# simple-loop-screws.net
KiCad netlist of a schematic drawn in EAGLE
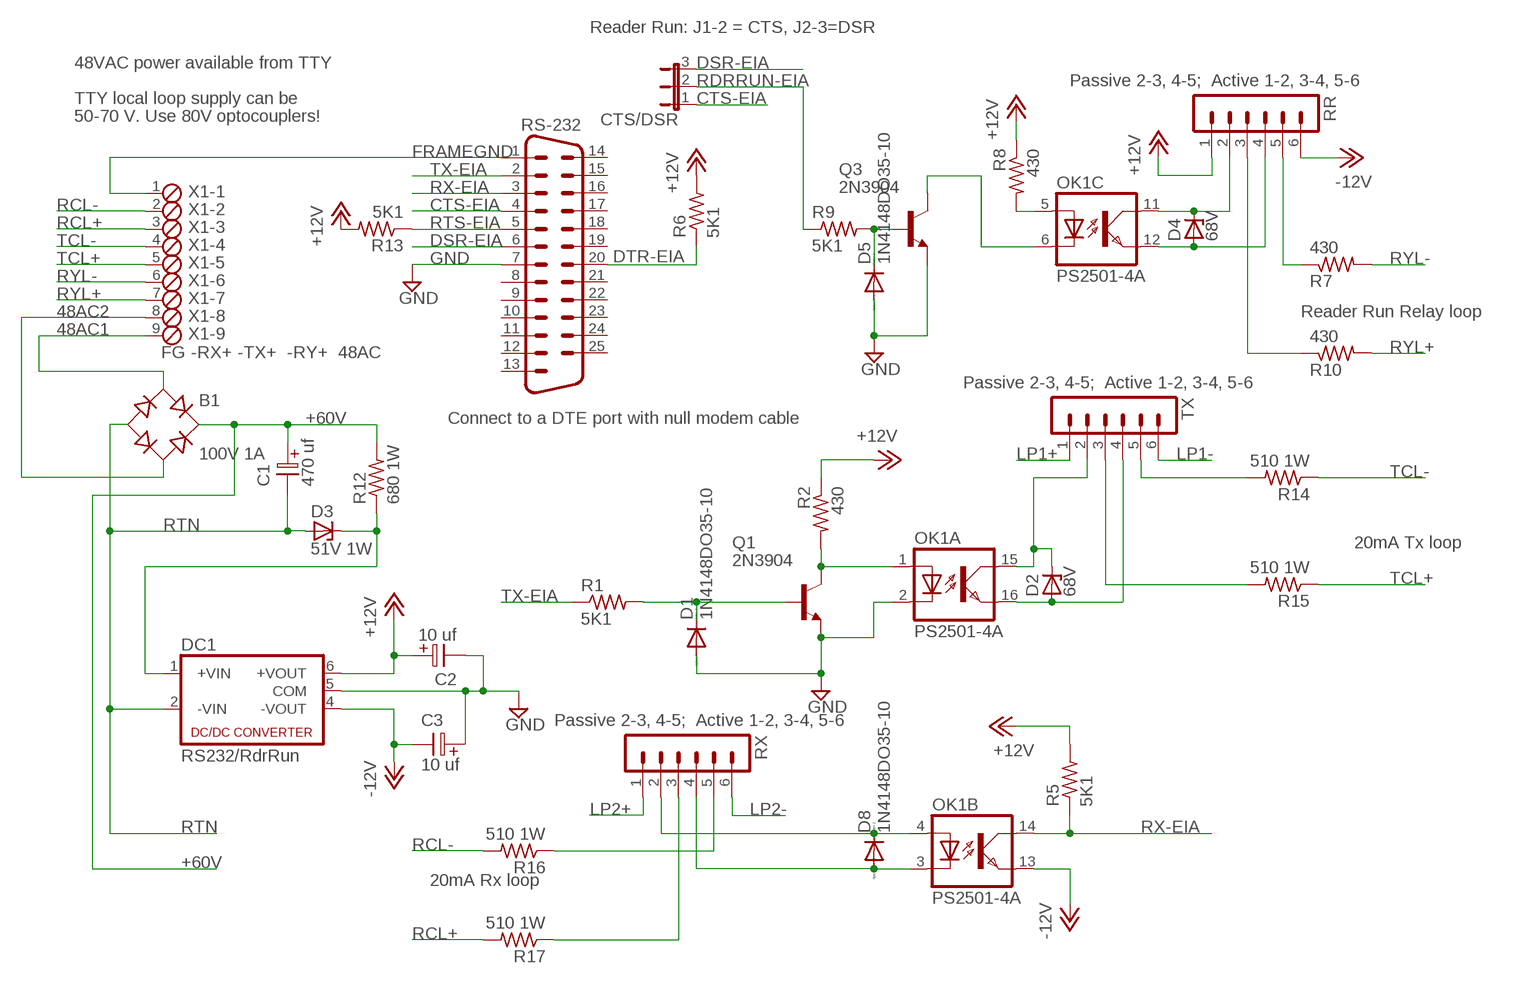
[diagram p0: schematic, sheet 1]
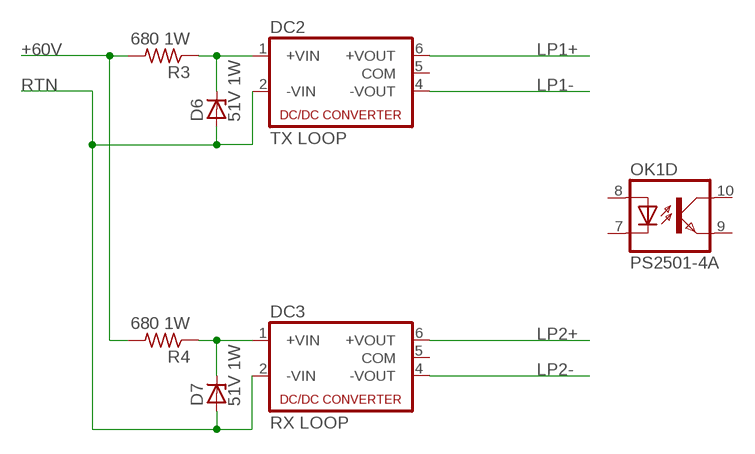
[diagram p1: schematic, sheet 2]

(export (version "E")
  (design (tool "Eeschema 10.0.6"))
  (components
    (comp (ref "D6")
      (value "51V 1W")
      (footprint "eagle-import:DO41Z10")
      (libsource (lib "eagle-import") (part "ZENER-DIODEDO41Z10"))
    )
    (comp (ref "D7")
      (value "51V 1W")
      (footprint "eagle-import:DO41Z10")
      (libsource (lib "eagle-import") (part "ZENER-DIODEDO41Z10"))
    )
    (comp (ref "DC2")
      (value "TX LOOP")
      (footprint "eagle-import:NMA")
      (fields (field (name "MF") "C & D TECHNOLOGIES, INC") (field (name "MPN") "NMA0515SC"))
      (libsource (lib "eagle-import") (part "NMA"))
    )
    (comp (ref "DC3")
      (value "RX LOOP")
      (footprint "eagle-import:NMA")
      (fields (field (name "MF") "C & D TECHNOLOGIES, INC") (field (name "MPN") "NMA0515SC"))
      (libsource (lib "eagle-import") (part "NMA"))
    )
    (comp (ref "OK1")
      (value "PS2501-4A")
      (footprint "eagle-import:DIL16")
      (fields (field (name "MF") "VISHAY/TELEFUNKEN") (field (name "MPN") "ILQ1"))
      (libsource (lib "eagle-import") (part "ILQ1"))
    )
    (comp (ref "R3")
      (value "680 1W")
      (footprint "eagle-import:P0817V")
      (libsource (lib "eagle-import") (part "R-US_0817/7V"))
    )
    (comp (ref "R4")
      (value "680 1W")
      (footprint "eagle-import:P0817V")
      (libsource (lib "eagle-import") (part "R-US_0817/7V"))
    )
    (comp (ref "B1")
      (value "100V 1A")
      (footprint "eagle-import:RB1A")
      (libsource (lib "eagle-import") (part "RB1A"))
    )
    (comp (ref "C1")
      (value "470 uf")
      (footprint "eagle-import:ES-7,5")
      (libsource (lib "eagle-import") (part "ELC-7,5"))
    )
    (comp (ref "C2")
      (value "10 uf")
      (footprint "eagle-import:ES-2,5")
      (libsource (lib "eagle-import") (part "ELC-2,5"))
    )
    (comp (ref "C3")
      (value "10 uf")
      (footprint "eagle-import:ES-2,5")
      (libsource (lib "eagle-import") (part "ELC-2,5"))
    )
    (comp (ref "CTS/DSR")
      (value "JP2E")
      (footprint "eagle-import:JP2")
      (libsource (lib "eagle-import") (part "JP2E"))
    )
    (comp (ref "D1")
      (value "1N4148DO35-10")
      (footprint "eagle-import:DO35-10")
      (libsource (lib "eagle-import") (part "1N4148DO35-10"))
    )
    (comp (ref "D2")
      (value "68V")
      (footprint "eagle-import:DO41Z10")
      (libsource (lib "eagle-import") (part "ZENER-DIODEDO41Z10"))
    )
    (comp (ref "D3")
      (value "51V 1W")
      (footprint "eagle-import:DO41Z10")
      (libsource (lib "eagle-import") (part "ZENER-DIODEDO41Z10"))
    )
    (comp (ref "D4")
      (value "68V")
      (footprint "eagle-import:DO41Z10")
      (libsource (lib "eagle-import") (part "ZENER-DIODEDO41Z10"))
    )
    (comp (ref "D5")
      (value "1N4148DO35-10")
      (footprint "eagle-import:DO35-10")
      (libsource (lib "eagle-import") (part "1N4148DO35-10"))
    )
    (comp (ref "D8")
      (value "1N4148DO35-10")
      (footprint "eagle-import:DO35-10")
      (libsource (lib "eagle-import") (part "1N4148DO35-10"))
    )
    (comp (ref "DC1")
      (value "RS232/RdrRun")
      (footprint "eagle-import:NMA")
      (fields (field (name "MF") "C & D TECHNOLOGIES, INC") (field (name "MPN") "NMA0515SC"))
      (libsource (lib "eagle-import") (part "NMA"))
    )
    (comp (ref "Q1")
      (value "2N3904")
      (footprint "eagle-import:TO92")
      (libsource (lib "eagle-import") (part "2N3904"))
    )
    (comp (ref "Q3")
      (value "2N3904")
      (footprint "eagle-import:TO92")
      (libsource (lib "eagle-import") (part "2N3904"))
    )
    (comp (ref "R1")
      (value "5K1")
      (footprint "eagle-import:0207_10")
      (libsource (lib "eagle-import") (part "R-US_0207/10"))
    )
    (comp (ref "R2")
      (value "430")
      (footprint "eagle-import:0207_10")
      (libsource (lib "eagle-import") (part "R-US_0207/10"))
    )
    (comp (ref "R5")
      (value "5K1")
      (footprint "eagle-import:0207_10")
      (libsource (lib "eagle-import") (part "R-US_0207/10"))
    )
    (comp (ref "R6")
      (value "5K1")
      (footprint "eagle-import:0207_10")
      (libsource (lib "eagle-import") (part "R-US_0207/10"))
    )
    (comp (ref "R7")
      (value "430")
      (footprint "eagle-import:0207_10")
      (libsource (lib "eagle-import") (part "R-US_0207/10"))
    )
    (comp (ref "R8")
      (value "430")
      (footprint "eagle-import:0207_10")
      (libsource (lib "eagle-import") (part "R-US_0207/10"))
    )
    (comp (ref "R9")
      (value "5K1")
      (footprint "eagle-import:0207_10")
      (libsource (lib "eagle-import") (part "R-US_0207/10"))
    )
    (comp (ref "R10")
      (value "430")
      (footprint "eagle-import:0207_10")
      (libsource (lib "eagle-import") (part "R-US_0207/10"))
    )
    (comp (ref "R12")
      (value "680 1W")
      (footprint "eagle-import:P0817V")
      (libsource (lib "eagle-import") (part "R-US_0817/7V"))
    )
    (comp (ref "R13")
      (value "5K1")
      (footprint "eagle-import:0207_10")
      (libsource (lib "eagle-import") (part "R-US_0207/10"))
    )
    (comp (ref "R14")
      (value "510 1W")
      (footprint "eagle-import:P0817V")
      (libsource (lib "eagle-import") (part "R-US_0817/7V"))
    )
    (comp (ref "R15")
      (value "510 1W")
      (footprint "eagle-import:P0817V")
      (libsource (lib "eagle-import") (part "R-US_0817/7V"))
    )
    (comp (ref "R16")
      (value "510 1W")
      (footprint "eagle-import:P0817V")
      (libsource (lib "eagle-import") (part "R-US_0817/7V"))
    )
    (comp (ref "R17")
      (value "510 1W")
      (footprint "eagle-import:P0817V")
      (libsource (lib "eagle-import") (part "R-US_0817/7V"))
    )
    (comp (ref "RR")
      (value "MA06-1")
      (footprint "eagle-import:MA06-1")
      (libsource (lib "eagle-import") (part "MA06-1"))
    )
    (comp (ref "RS-232")
      (value "M25H")
      (footprint "eagle-import:M25H")
      (libsource (lib "eagle-import") (part "M25H"))
    )
    (comp (ref "RX")
      (value "MA06-1")
      (footprint "eagle-import:MA06-1")
      (libsource (lib "eagle-import") (part "MA06-1"))
    )
    (comp (ref "TX")
      (value "MA06-1")
      (footprint "eagle-import:MA06-1")
      (libsource (lib "eagle-import") (part "MA06-1"))
    )
    (comp (ref "X1")
      (value "FG -RX+ -TX+ -RY+ 48AC")
      (footprint "eagle-import:9POL254")
      (libsource (lib "eagle-import") (part "MPT9"))
    )
  )
  (nets
    (net (code "1") (name "+12V") (class "Default")
      (node (ref "C2") (pin "1") (pinfunction "1_1") (pintype "passive"))
      (node (ref "DC1") (pin "6") (pinfunction "+VOUT_6") (pintype "passive"))
      (node (ref "R13") (pin "2") (pinfunction "2_2") (pintype "passive"))
      (node (ref "R2") (pin "1") (pinfunction "1_1") (pintype "passive"))
      (node (ref "R5") (pin "2") (pinfunction "2_2") (pintype "passive"))
      (node (ref "R6") (pin "2") (pinfunction "2_2") (pintype "passive"))
      (node (ref "R8") (pin "1") (pinfunction "1_1") (pintype "passive"))
      (node (ref "RR") (pin "1") (pinfunction "1_1") (pintype "passive"))
    )
    (net (code "2") (name "+60V") (class "Default")
      (node (ref "B1") (pin "+") (pinfunction "+_+") (pintype "passive"))
      (node (ref "C1") (pin "1") (pinfunction "1_1") (pintype "passive"))
      (node (ref "R12") (pin "2") (pinfunction "2_2") (pintype "passive"))
      (node (ref "R3") (pin "2") (pinfunction "2_2") (pintype "passive"))
      (node (ref "R4") (pin "2") (pinfunction "2_2") (pintype "passive"))
    )
    (net (code "3") (name "-12V") (class "Default")
      (node (ref "C3") (pin "2") (pinfunction "2_2") (pintype "passive"))
      (node (ref "DC1") (pin "4") (pinfunction "-VOUT_4") (pintype "passive"))
      (node (ref "OK1") (pin "13") (pinfunction "EMIT_13") (pintype "passive"))
      (node (ref "RR") (pin "6") (pinfunction "6_6") (pintype "passive"))
    )
    (net (code "4") (name "48AC1") (class "Default")
      (node (ref "B1") (pin "AC1") (pinfunction "AC1_AC1") (pintype "passive"))
      (node (ref "X1") (pin "9") (pinfunction "1_9") (pintype "passive"))
    )
    (net (code "5") (name "48AC2") (class "Default")
      (node (ref "B1") (pin "AC2") (pinfunction "AC2_AC2") (pintype "passive"))
      (node (ref "X1") (pin "8") (pinfunction "1_8") (pintype "passive"))
    )
    (net (code "6") (name "CTS-EIA") (class "Default")
      (node (ref "CTS/DSR") (pin "1") (pinfunction "1_1") (pintype "passive"))
      (node (ref "RS-232") (pin "4") (pinfunction "4_4") (pintype "passive"))
    )
    (net (code "7") (name "DSR-EIA") (class "Default")
      (node (ref "CTS/DSR") (pin "3") (pinfunction "3_3") (pintype "passive"))
      (node (ref "RS-232") (pin "6") (pinfunction "6_6") (pintype "passive"))
    )
    (net (code "8") (name "DTR-EIA") (class "Default")
      (node (ref "R6") (pin "1") (pinfunction "1_1") (pintype "passive"))
      (node (ref "RS-232") (pin "20") (pinfunction "20_20") (pintype "passive"))
    )
    (net (code "9") (name "FRAMEGND") (class "Default")
      (node (ref "RS-232") (pin "1") (pinfunction "1_1") (pintype "passive"))
      (node (ref "X1") (pin "1") (pinfunction "1_1") (pintype "passive"))
    )
    (net (code "10") (name "GND") (class "Default")
      (node (ref "C2") (pin "2") (pinfunction "2_2") (pintype "passive"))
      (node (ref "C3") (pin "1") (pinfunction "1_1") (pintype "passive"))
      (node (ref "D1") (pin "A") (pinfunction "A_A") (pintype "passive"))
      (node (ref "D5") (pin "A") (pinfunction "A_A") (pintype "passive"))
      (node (ref "DC1") (pin "5") (pinfunction "COM_5") (pintype "passive"))
      (node (ref "OK1") (pin "2") (pinfunction "C_2") (pintype "passive"))
      (node (ref "Q1") (pin "3") (pinfunction "E_3") (pintype "passive"))
      (node (ref "Q3") (pin "3") (pinfunction "E_3") (pintype "passive"))
      (node (ref "RS-232") (pin "7") (pinfunction "7_7") (pintype "passive"))
    )
    (net (code "11") (name "LP1+") (class "Default")
      (node (ref "DC2") (pin "6") (pinfunction "+VOUT_6") (pintype "passive"))
      (node (ref "TX") (pin "1") (pinfunction "1_1") (pintype "passive"))
    )
    (net (code "12") (name "LP1-") (class "Default")
      (node (ref "DC2") (pin "4") (pinfunction "-VOUT_4") (pintype "passive"))
      (node (ref "TX") (pin "6") (pinfunction "6_6") (pintype "passive"))
    )
    (net (code "13") (name "LP2+") (class "Default")
      (node (ref "DC3") (pin "6") (pinfunction "+VOUT_6") (pintype "passive"))
      (node (ref "RX") (pin "1") (pinfunction "1_1") (pintype "passive"))
    )
    (net (code "14") (name "LP2-") (class "Default")
      (node (ref "DC3") (pin "4") (pinfunction "-VOUT_4") (pintype "passive"))
      (node (ref "RX") (pin "6") (pinfunction "6_6") (pintype "passive"))
    )
    (net (code "15") (name "Net-(DC1-+VIN)") (class "Default")
      (node (ref "D3") (pin "C") (pinfunction "C_C") (pintype "passive"))
      (node (ref "DC1") (pin "1") (pinfunction "+VIN_1") (pintype "passive"))
      (node (ref "R12") (pin "1") (pinfunction "1_1") (pintype "passive"))
    )
    (net (code "16") (name "Net-(DC2-+VIN)") (class "Default")
      (node (ref "D6") (pin "C") (pinfunction "C_C") (pintype "passive"))
      (node (ref "DC2") (pin "1") (pinfunction "+VIN_1") (pintype "passive"))
      (node (ref "R3") (pin "1") (pinfunction "1_1") (pintype "passive"))
    )
    (net (code "17") (name "Net-(DC3-+VIN)") (class "Default")
      (node (ref "D7") (pin "C") (pinfunction "C_C") (pintype "passive"))
      (node (ref "DC3") (pin "1") (pinfunction "+VIN_1") (pintype "passive"))
      (node (ref "R4") (pin "1") (pinfunction "1_1") (pintype "passive"))
    )
    (net (code "18") (name "Net-(OK1A-A)") (class "Default")
      (node (ref "OK1") (pin "1") (pinfunction "A_1") (pintype "passive"))
      (node (ref "Q1") (pin "1") (pinfunction "C_1") (pintype "passive"))
      (node (ref "R2") (pin "2") (pinfunction "2_2") (pintype "passive"))
    )
    (net (code "19") (name "Net-(OK1A-COL)") (class "Default")
      (node (ref "D2") (pin "C") (pinfunction "C_C") (pintype "passive"))
      (node (ref "OK1") (pin "15") (pinfunction "COL_15") (pintype "passive"))
      (node (ref "TX") (pin "2") (pinfunction "2_2") (pintype "passive"))
    )
    (net (code "20") (name "Net-(OK1A-EMIT)") (class "Default")
      (node (ref "D2") (pin "A") (pinfunction "A_A") (pintype "passive"))
      (node (ref "OK1") (pin "16") (pinfunction "EMIT_16") (pintype "passive"))
      (node (ref "TX") (pin "4") (pinfunction "4_4") (pintype "passive"))
    )
    (net (code "21") (name "Net-(OK1B-A)") (class "Default")
      (node (ref "D8") (pin "C") (pinfunction "C_C") (pintype "passive"))
      (node (ref "OK1") (pin "4") (pinfunction "A_4") (pintype "passive"))
      (node (ref "RX") (pin "2") (pinfunction "2_2") (pintype "passive"))
    )
    (net (code "22") (name "Net-(OK1B-C)") (class "Default")
      (node (ref "D8") (pin "A") (pinfunction "A_A") (pintype "passive"))
      (node (ref "OK1") (pin "3") (pinfunction "C_3") (pintype "passive"))
      (node (ref "RX") (pin "4") (pinfunction "4_4") (pintype "passive"))
    )
    (net (code "23") (name "Net-(OK1C-A)") (class "Default")
      (node (ref "OK1") (pin "5") (pinfunction "A_5") (pintype "passive"))
      (node (ref "R8") (pin "2") (pinfunction "2_2") (pintype "passive"))
    )
    (net (code "24") (name "Net-(OK1C-C)") (class "Default")
      (node (ref "OK1") (pin "6") (pinfunction "C_6") (pintype "passive"))
      (node (ref "Q3") (pin "1") (pinfunction "C_1") (pintype "passive"))
    )
    (net (code "25") (name "Net-(OK1C-COL)") (class "Default")
      (node (ref "D4") (pin "C") (pinfunction "C_C") (pintype "passive"))
      (node (ref "OK1") (pin "11") (pinfunction "COL_11") (pintype "passive"))
      (node (ref "RR") (pin "2") (pinfunction "2_2") (pintype "passive"))
    )
    (net (code "26") (name "Net-(OK1C-EMIT)") (class "Default")
      (node (ref "D4") (pin "A") (pinfunction "A_A") (pintype "passive"))
      (node (ref "OK1") (pin "12") (pinfunction "EMIT_12") (pintype "passive"))
      (node (ref "RR") (pin "4") (pinfunction "4_4") (pintype "passive"))
    )
    (net (code "27") (name "Net-(Q1-B)") (class "Default")
      (node (ref "D1") (pin "C") (pinfunction "C_C") (pintype "passive"))
      (node (ref "Q1") (pin "2") (pinfunction "B_2") (pintype "passive"))
      (node (ref "R1") (pin "2") (pinfunction "2_2") (pintype "passive"))
    )
    (net (code "28") (name "Net-(Q3-B)") (class "Default")
      (node (ref "D5") (pin "C") (pinfunction "C_C") (pintype "passive"))
      (node (ref "Q3") (pin "2") (pinfunction "B_2") (pintype "passive"))
      (node (ref "R9") (pin "2") (pinfunction "2_2") (pintype "passive"))
    )
    (net (code "29") (name "Net-(R7-Pad1)") (class "Default")
      (node (ref "R7") (pin "1") (pinfunction "1_1") (pintype "passive"))
      (node (ref "RR") (pin "5") (pinfunction "5_5") (pintype "passive"))
    )
    (net (code "30") (name "Net-(R10-Pad1)") (class "Default")
      (node (ref "R10") (pin "1") (pinfunction "1_1") (pintype "passive"))
      (node (ref "RR") (pin "3") (pinfunction "3_3") (pintype "passive"))
    )
    (net (code "31") (name "Net-(R14-Pad2)") (class "Default")
      (node (ref "R14") (pin "2") (pinfunction "2_2") (pintype "passive"))
      (node (ref "TX") (pin "5") (pinfunction "5_5") (pintype "passive"))
    )
    (net (code "32") (name "Net-(R15-Pad2)") (class "Default")
      (node (ref "R15") (pin "2") (pinfunction "2_2") (pintype "passive"))
      (node (ref "TX") (pin "3") (pinfunction "3_3") (pintype "passive"))
    )
    (net (code "33") (name "Net-(R16-Pad1)") (class "Default")
      (node (ref "R16") (pin "1") (pinfunction "1_1") (pintype "passive"))
      (node (ref "RX") (pin "5") (pinfunction "5_5") (pintype "passive"))
    )
    (net (code "34") (name "Net-(R17-Pad1)") (class "Default")
      (node (ref "R17") (pin "1") (pinfunction "1_1") (pintype "passive"))
      (node (ref "RX") (pin "3") (pinfunction "3_3") (pintype "passive"))
    )
    (net (code "35") (name "RCL+") (class "Default")
      (node (ref "R17") (pin "2") (pinfunction "2_2") (pintype "passive"))
      (node (ref "X1") (pin "3") (pinfunction "1_3") (pintype "passive"))
    )
    (net (code "36") (name "RCL-") (class "Default")
      (node (ref "R16") (pin "2") (pinfunction "2_2") (pintype "passive"))
      (node (ref "X1") (pin "2") (pinfunction "1_2") (pintype "passive"))
    )
    (net (code "37") (name "RDRRUN-EIA") (class "Default")
      (node (ref "CTS/DSR") (pin "2") (pinfunction "2_2") (pintype "passive"))
      (node (ref "R9") (pin "1") (pinfunction "1_1") (pintype "passive"))
    )
    (net (code "38") (name "RTN") (class "Default")
      (node (ref "B1") (pin "-") (pinfunction "-_-") (pintype "passive"))
      (node (ref "C1") (pin "2") (pinfunction "2_2") (pintype "passive"))
      (node (ref "D3") (pin "A") (pinfunction "A_A") (pintype "passive"))
      (node (ref "D6") (pin "A") (pinfunction "A_A") (pintype "passive"))
      (node (ref "D7") (pin "A") (pinfunction "A_A") (pintype "passive"))
      (node (ref "DC1") (pin "2") (pinfunction "-VIN_2") (pintype "passive"))
      (node (ref "DC2") (pin "2") (pinfunction "-VIN_2") (pintype "passive"))
      (node (ref "DC3") (pin "2") (pinfunction "-VIN_2") (pintype "passive"))
    )
    (net (code "39") (name "RTS-EIA") (class "Default")
      (node (ref "R13") (pin "1") (pinfunction "1_1") (pintype "passive"))
      (node (ref "RS-232") (pin "5") (pinfunction "5_5") (pintype "passive"))
    )
    (net (code "40") (name "RX-EIA") (class "Default")
      (node (ref "OK1") (pin "14") (pinfunction "COL_14") (pintype "passive"))
      (node (ref "R5") (pin "1") (pinfunction "1_1") (pintype "passive"))
      (node (ref "RS-232") (pin "3") (pinfunction "3_3") (pintype "passive"))
    )
    (net (code "41") (name "RYL+") (class "Default")
      (node (ref "R10") (pin "2") (pinfunction "2_2") (pintype "passive"))
      (node (ref "X1") (pin "7") (pinfunction "1_7") (pintype "passive"))
    )
    (net (code "42") (name "RYL-") (class "Default")
      (node (ref "R7") (pin "2") (pinfunction "2_2") (pintype "passive"))
      (node (ref "X1") (pin "6") (pinfunction "1_6") (pintype "passive"))
    )
    (net (code "43") (name "TCL+") (class "Default")
      (node (ref "R15") (pin "1") (pinfunction "1_1") (pintype "passive"))
      (node (ref "X1") (pin "5") (pinfunction "1_5") (pintype "passive"))
    )
    (net (code "44") (name "TCL-") (class "Default")
      (node (ref "R14") (pin "1") (pinfunction "1_1") (pintype "passive"))
      (node (ref "X1") (pin "4") (pinfunction "1_4") (pintype "passive"))
    )
    (net (code "45") (name "TX-EIA") (class "Default")
      (node (ref "R1") (pin "1") (pinfunction "1_1") (pintype "passive"))
      (node (ref "RS-232") (pin "2") (pinfunction "2_2") (pintype "passive"))
    )
    (net (code "46") (name "unconnected-(DC2-COM-Pad5)") (class "Default")
      (node (ref "DC2") (pin "5") (pinfunction "COM_5") (pintype "passive"))
    )
    (net (code "47") (name "unconnected-(DC3-COM-Pad5)") (class "Default")
      (node (ref "DC3") (pin "5") (pinfunction "COM_5") (pintype "passive"))
    )
    (net (code "48") (name "unconnected-(OK1D-A-Pad8)") (class "Default")
      (node (ref "OK1") (pin "8") (pinfunction "A_8") (pintype "passive"))
    )
    (net (code "49") (name "unconnected-(OK1D-C-Pad7)") (class "Default")
      (node (ref "OK1") (pin "7") (pinfunction "C_7") (pintype "passive"))
    )
    (net (code "50") (name "unconnected-(OK1D-COL-Pad10)") (class "Default")
      (node (ref "OK1") (pin "10") (pinfunction "COL_10") (pintype "passive"))
    )
    (net (code "51") (name "unconnected-(OK1D-EMIT-Pad9)") (class "Default")
      (node (ref "OK1") (pin "9") (pinfunction "EMIT_9") (pintype "passive"))
    )
    (net (code "52") (name "unconnected-(RS-232-Pad8)") (class "Default")
      (node (ref "RS-232") (pin "8") (pinfunction "8_8") (pintype "passive"))
    )
    (net (code "53") (name "unconnected-(RS-232-Pad9)") (class "Default")
      (node (ref "RS-232") (pin "9") (pinfunction "9_9") (pintype "passive"))
    )
    (net (code "54") (name "unconnected-(RS-232-Pad10)") (class "Default")
      (node (ref "RS-232") (pin "10") (pinfunction "10_10") (pintype "passive"))
    )
    (net (code "55") (name "unconnected-(RS-232-Pad11)") (class "Default")
      (node (ref "RS-232") (pin "11") (pinfunction "11_11") (pintype "passive"))
    )
    (net (code "56") (name "unconnected-(RS-232-Pad12)") (class "Default")
      (node (ref "RS-232") (pin "12") (pinfunction "12_12") (pintype "passive"))
    )
    (net (code "57") (name "unconnected-(RS-232-Pad13)") (class "Default")
      (node (ref "RS-232") (pin "13") (pinfunction "13_13") (pintype "passive"))
    )
    (net (code "58") (name "unconnected-(RS-232-Pad14)") (class "Default")
      (node (ref "RS-232") (pin "14") (pinfunction "14_14") (pintype "passive"))
    )
    (net (code "59") (name "unconnected-(RS-232-Pad15)") (class "Default")
      (node (ref "RS-232") (pin "15") (pinfunction "15_15") (pintype "passive"))
    )
    (net (code "60") (name "unconnected-(RS-232-Pad16)") (class "Default")
      (node (ref "RS-232") (pin "16") (pinfunction "16_16") (pintype "passive"))
    )
    (net (code "61") (name "unconnected-(RS-232-Pad17)") (class "Default")
      (node (ref "RS-232") (pin "17") (pinfunction "17_17") (pintype "passive"))
    )
    (net (code "62") (name "unconnected-(RS-232-Pad18)") (class "Default")
      (node (ref "RS-232") (pin "18") (pinfunction "18_18") (pintype "passive"))
    )
    (net (code "63") (name "unconnected-(RS-232-Pad19)") (class "Default")
      (node (ref "RS-232") (pin "19") (pinfunction "19_19") (pintype "passive"))
    )
    (net (code "64") (name "unconnected-(RS-232-Pad21)") (class "Default")
      (node (ref "RS-232") (pin "21") (pinfunction "21_21") (pintype "passive"))
    )
    (net (code "65") (name "unconnected-(RS-232-Pad22)") (class "Default")
      (node (ref "RS-232") (pin "22") (pinfunction "22_22") (pintype "passive"))
    )
    (net (code "66") (name "unconnected-(RS-232-Pad23)") (class "Default")
      (node (ref "RS-232") (pin "23") (pinfunction "23_23") (pintype "passive"))
    )
    (net (code "67") (name "unconnected-(RS-232-Pad24)") (class "Default")
      (node (ref "RS-232") (pin "24") (pinfunction "24_24") (pintype "passive"))
    )
    (net (code "68") (name "unconnected-(RS-232-Pad25)") (class "Default")
      (node (ref "RS-232") (pin "25") (pinfunction "25_25") (pintype "passive"))
    )
  )
)
